# rcl_mini.net
KiCad netlist of a schematic drawn in EAGLE
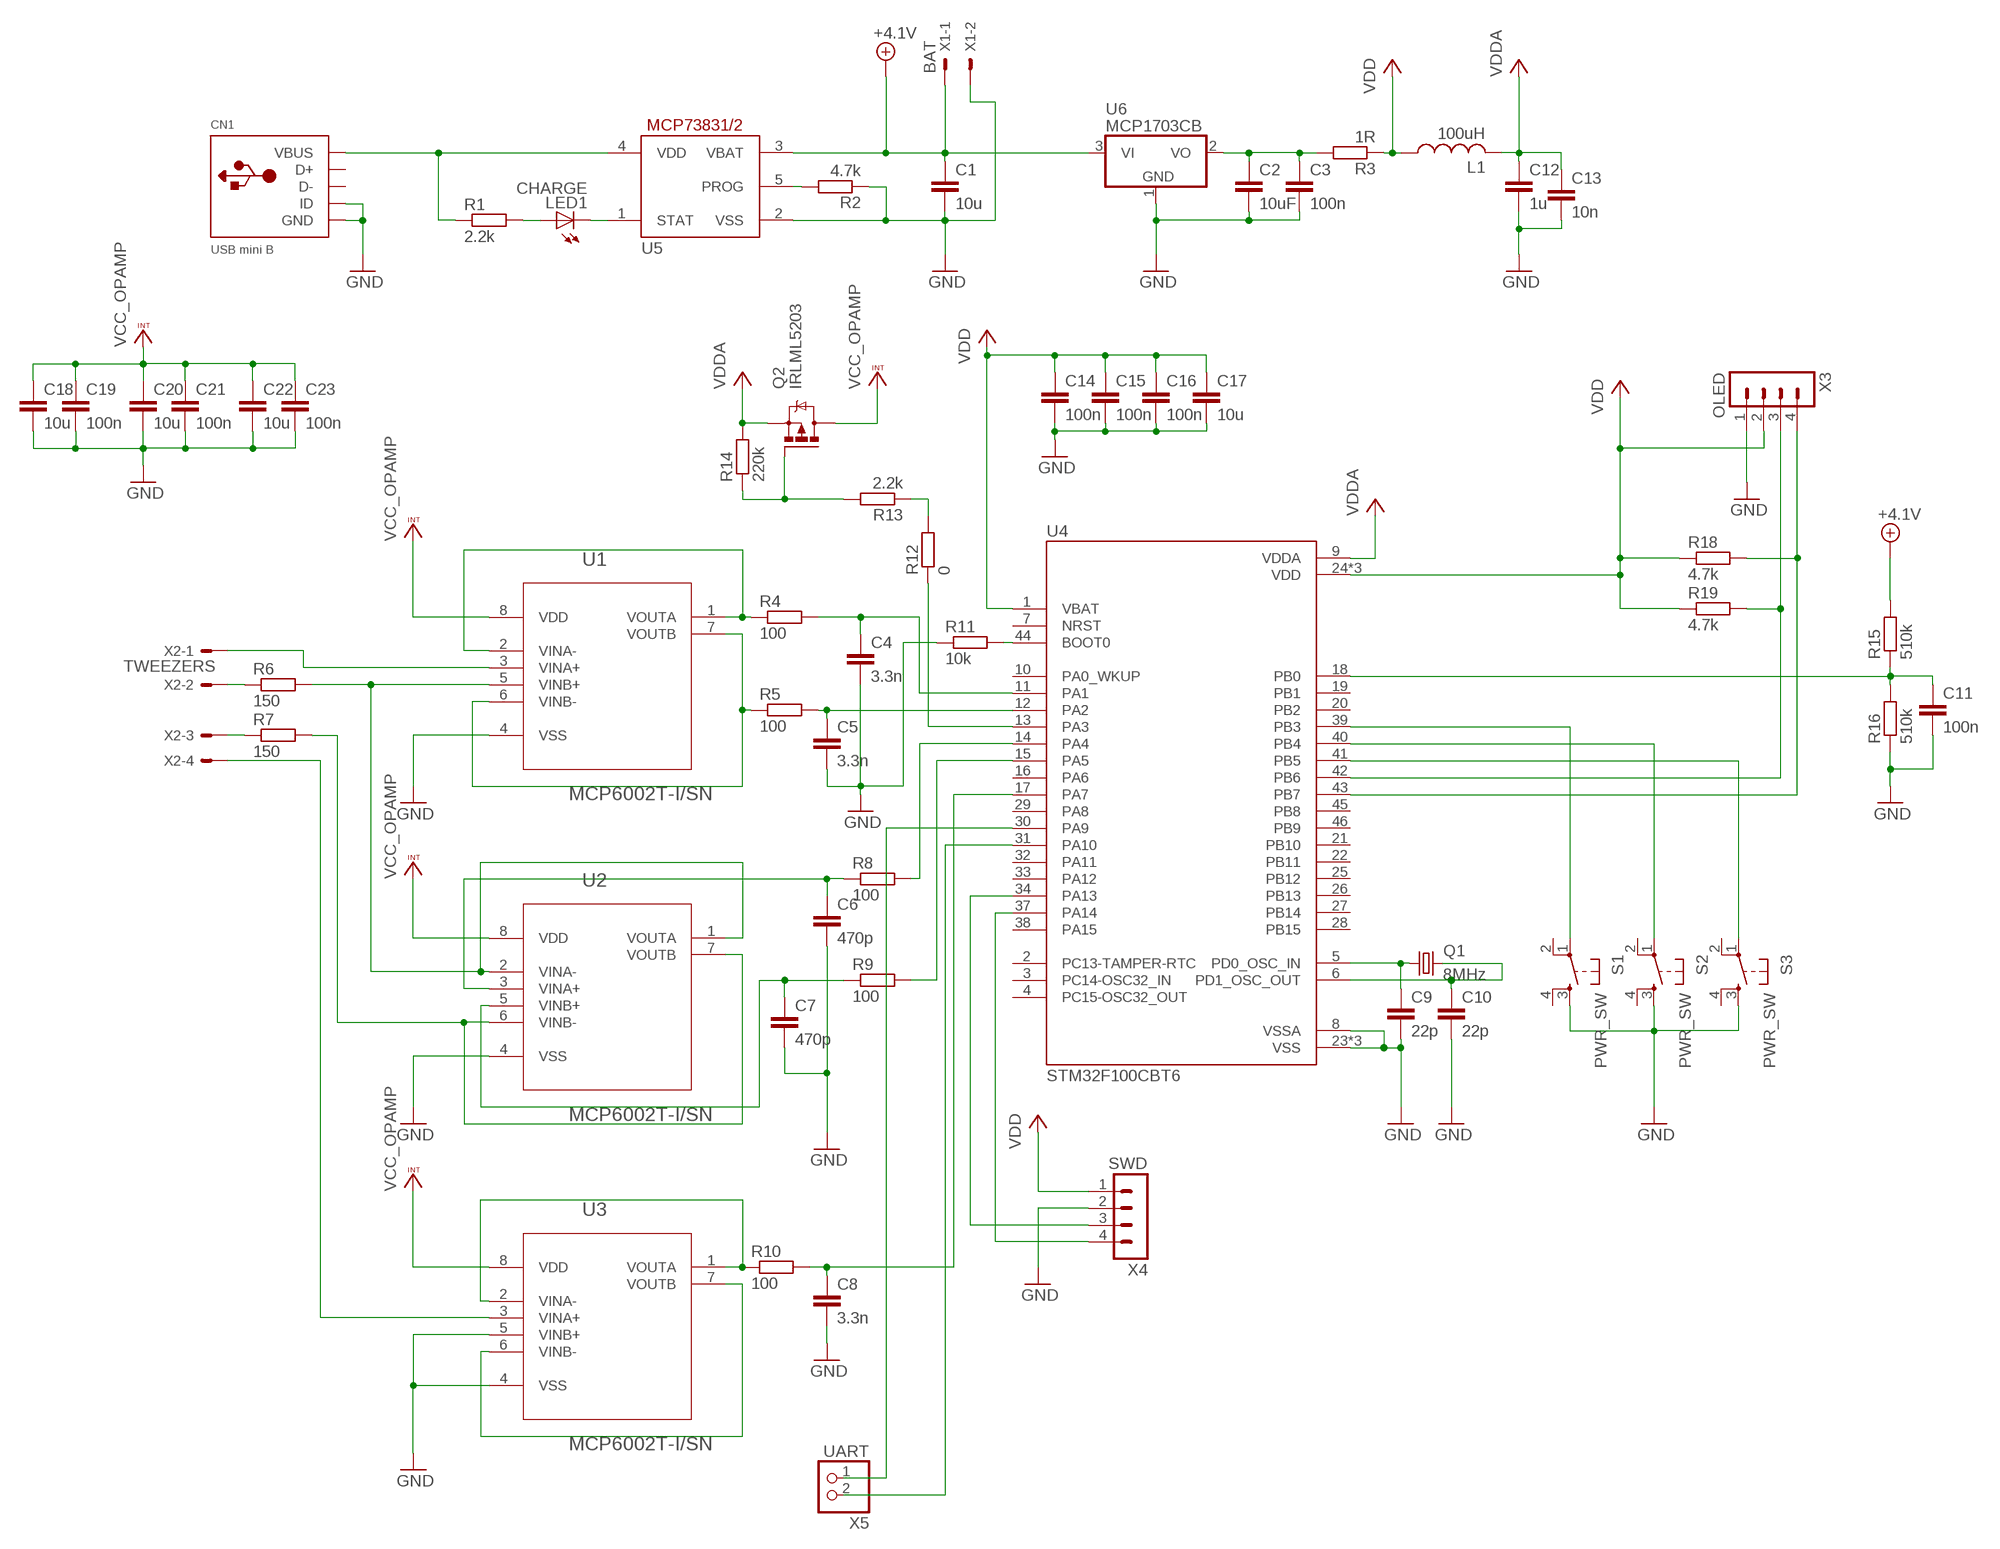
[diagram p0: schematic, sheet 1]

(export (version "E")
  (design (tool "Eeschema 10.0.6"))
  (components
    (comp (ref "C1")
      (value "10u")
      (footprint "eagle-import:C0805")
      (libsource (lib "eagle-import") (part "C-EUC0805"))
    )
    (comp (ref "C2")
      (value "10uF")
      (footprint "eagle-import:C0805")
      (libsource (lib "eagle-import") (part "C-EUC0805"))
    )
    (comp (ref "C3")
      (value "100n")
      (footprint "eagle-import:C0805")
      (libsource (lib "eagle-import") (part "C-EUC0805"))
    )
    (comp (ref "C4")
      (value "3.3n")
      (footprint "eagle-import:C0805")
      (libsource (lib "eagle-import") (part "C-EUC0805"))
    )
    (comp (ref "C5")
      (value "3.3n")
      (footprint "eagle-import:C0805")
      (libsource (lib "eagle-import") (part "C-EUC0805"))
    )
    (comp (ref "C6")
      (value "470p")
      (footprint "eagle-import:C0805")
      (libsource (lib "eagle-import") (part "C-EUC0805"))
    )
    (comp (ref "C7")
      (value "470p")
      (footprint "eagle-import:C0805")
      (libsource (lib "eagle-import") (part "C-EUC0805"))
    )
    (comp (ref "C8")
      (value "3.3n")
      (footprint "eagle-import:C0805")
      (libsource (lib "eagle-import") (part "C-EUC0805"))
    )
    (comp (ref "C9")
      (value "22p")
      (footprint "eagle-import:C0805")
      (libsource (lib "eagle-import") (part "C-EUC0805"))
    )
    (comp (ref "C10")
      (value "22p")
      (footprint "eagle-import:C0805")
      (libsource (lib "eagle-import") (part "C-EUC0805"))
    )
    (comp (ref "C11")
      (value "100n")
      (footprint "eagle-import:C0805")
      (libsource (lib "eagle-import") (part "C-EUC0805"))
    )
    (comp (ref "C12")
      (value "1u")
      (footprint "eagle-import:C0805")
      (libsource (lib "eagle-import") (part "C-EUC0805"))
    )
    (comp (ref "C13")
      (value "10n")
      (footprint "eagle-import:C0805")
      (libsource (lib "eagle-import") (part "C-EUC0805"))
    )
    (comp (ref "C14")
      (value "100n")
      (footprint "eagle-import:C0805")
      (libsource (lib "eagle-import") (part "C-EUC0805"))
    )
    (comp (ref "C15")
      (value "100n")
      (footprint "eagle-import:C0805")
      (libsource (lib "eagle-import") (part "C-EUC0805"))
    )
    (comp (ref "C16")
      (value "100n")
      (footprint "eagle-import:C0805")
      (libsource (lib "eagle-import") (part "C-EUC0805"))
    )
    (comp (ref "C17")
      (value "10u")
      (footprint "eagle-import:C0805")
      (libsource (lib "eagle-import") (part "C-EUC0805"))
    )
    (comp (ref "C18")
      (value "10u")
      (footprint "eagle-import:C0805")
      (libsource (lib "eagle-import") (part "C-EUC0805"))
    )
    (comp (ref "C19")
      (value "100n")
      (footprint "eagle-import:C0805")
      (libsource (lib "eagle-import") (part "C-EUC0805"))
    )
    (comp (ref "C20")
      (value "10u")
      (footprint "eagle-import:C0805")
      (libsource (lib "eagle-import") (part "C-EUC0805"))
    )
    (comp (ref "C21")
      (value "100n")
      (footprint "eagle-import:C0805")
      (libsource (lib "eagle-import") (part "C-EUC0805"))
    )
    (comp (ref "C22")
      (value "10u")
      (footprint "eagle-import:C0805")
      (libsource (lib "eagle-import") (part "C-EUC0805"))
    )
    (comp (ref "C23")
      (value "100n")
      (footprint "eagle-import:C0805")
      (libsource (lib "eagle-import") (part "C-EUC0805"))
    )
    (comp (ref "CN1")
      (value "USB mini B")
      (footprint "eagle-import:USB-MINIB")
      (libsource (lib "eagle-import") (part "USBMINIB"))
    )
    (comp (ref "L1")
      (value "100uH")
      (footprint "eagle-import:L3216C")
      (libsource (lib "eagle-import") (part "L-USL3216C"))
    )
    (comp (ref "LED1")
      (value "CHARGE")
      (footprint "eagle-import:CHIPLED_1206")
      (libsource (lib "eagle-import") (part "LEDCHIPLED_1206"))
    )
    (comp (ref "Q1")
      (value "8MHz")
      (footprint "eagle-import:HC49UP")
      (libsource (lib "eagle-import") (part "CRYSTALHC49UP"))
    )
    (comp (ref "Q2")
      (value "IRLML5203")
      (footprint "eagle-import:MICRO3")
      (libsource (lib "eagle-import") (part "IRLML5203"))
    )
    (comp (ref "R1")
      (value "2.2k")
      (footprint "eagle-import:M0805")
      (libsource (lib "eagle-import") (part "R-EU_M0805"))
    )
    (comp (ref "R2")
      (value "4.7k")
      (footprint "eagle-import:M0805")
      (libsource (lib "eagle-import") (part "R-EU_M0805"))
    )
    (comp (ref "R3")
      (value "1R")
      (footprint "eagle-import:M0805")
      (libsource (lib "eagle-import") (part "R-EU_M0805"))
    )
    (comp (ref "R4")
      (value "100")
      (footprint "eagle-import:M0805")
      (libsource (lib "eagle-import") (part "R-EU_M0805"))
    )
    (comp (ref "R5")
      (value "100")
      (footprint "eagle-import:M0805")
      (libsource (lib "eagle-import") (part "R-EU_M0805"))
    )
    (comp (ref "R6")
      (value "150")
      (footprint "eagle-import:M0805")
      (libsource (lib "eagle-import") (part "R-EU_M0805"))
    )
    (comp (ref "R7")
      (value "150")
      (footprint "eagle-import:M0805")
      (libsource (lib "eagle-import") (part "R-EU_M0805"))
    )
    (comp (ref "R8")
      (value "100")
      (footprint "eagle-import:M0805")
      (libsource (lib "eagle-import") (part "R-EU_M0805"))
    )
    (comp (ref "R9")
      (value "100")
      (footprint "eagle-import:M0805")
      (libsource (lib "eagle-import") (part "R-EU_M0805"))
    )
    (comp (ref "R10")
      (value "100")
      (footprint "eagle-import:M0805")
      (libsource (lib "eagle-import") (part "R-EU_M0805"))
    )
    (comp (ref "R11")
      (value "10k")
      (footprint "eagle-import:M0805")
      (libsource (lib "eagle-import") (part "R-EU_M0805"))
    )
    (comp (ref "R12")
      (value "0")
      (footprint "eagle-import:R1206")
      (libsource (lib "eagle-import") (part "R-EU_R1206"))
    )
    (comp (ref "R13")
      (value "2.2k")
      (footprint "eagle-import:M0805")
      (libsource (lib "eagle-import") (part "R-EU_M0805"))
    )
    (comp (ref "R14")
      (value "220k")
      (footprint "eagle-import:M0805")
      (libsource (lib "eagle-import") (part "R-EU_M0805"))
    )
    (comp (ref "R15")
      (value "510k")
      (footprint "eagle-import:M0805")
      (libsource (lib "eagle-import") (part "R-EU_M0805"))
    )
    (comp (ref "R16")
      (value "510k")
      (footprint "eagle-import:M0805")
      (libsource (lib "eagle-import") (part "R-EU_M0805"))
    )
    (comp (ref "R18")
      (value "4.7k")
      (footprint "eagle-import:M0805")
      (libsource (lib "eagle-import") (part "R-EU_M0805"))
    )
    (comp (ref "R19")
      (value "4.7k")
      (footprint "eagle-import:M0805")
      (libsource (lib "eagle-import") (part "R-EU_M0805"))
    )
    (comp (ref "S1")
      (value "PWR_SW")
      (footprint "eagle-import:DTS-6")
      (libsource (lib "eagle-import") (part "DTS-6"))
    )
    (comp (ref "S2")
      (value "PWR_SW")
      (footprint "eagle-import:DTS-6")
      (libsource (lib "eagle-import") (part "DTS-6"))
    )
    (comp (ref "S3")
      (value "PWR_SW")
      (footprint "eagle-import:DTS-6")
      (libsource (lib "eagle-import") (part "DTS-6"))
    )
    (comp (ref "U1")
      (value "MCP6002T-I/SN")
      (footprint "eagle-import:SOIC127P600X175-8N")
      (fields (field (name "MF") "Microchip") (field (name "MP") "MCP6002-E/SN"))
      (libsource (lib "eagle-import") (part "MCP6002-E/SN"))
    )
    (comp (ref "U2")
      (value "MCP6002T-I/SN")
      (footprint "eagle-import:SOIC127P600X175-8N")
      (fields (field (name "MF") "Microchip") (field (name "MP") "MCP6002-E/SN"))
      (libsource (lib "eagle-import") (part "MCP6002-E/SN"))
    )
    (comp (ref "U3")
      (value "MCP6002T-I/SN")
      (footprint "eagle-import:SOIC127P600X175-8N")
      (fields (field (name "MF") "Microchip") (field (name "MP") "MCP6002-E/SN"))
      (libsource (lib "eagle-import") (part "MCP6002-E/SN"))
    )
    (comp (ref "U4")
      (value "STM32F100CBT6")
      (footprint "eagle-import:QFP50P900X900X160-48N")
      (fields (field (name "MF") "STMicroelectronics") (field (name "MP") "STM32F103C8T6"))
      (libsource (lib "eagle-import") (part "STM32F103C8T6"))
    )
    (comp (ref "U5")
      (value "MCP73831/OT")
      (footprint "eagle-import:SOT23-5L")
      (libsource (lib "eagle-import") (part "MCP73831/OT"))
    )
    (comp (ref "U6")
      (value "MCP1703CB")
      (footprint "eagle-import:SOT23")
      (libsource (lib "eagle-import") (part "MCP1703CB"))
    )
    (comp (ref "UART")
      (value "X5")
      (footprint "eagle-import:1X02")
      (libsource (lib "eagle-import") (part "PINHD-1X2"))
    )
    (comp (ref "X1")
      (value "BAT")
      (footprint "eagle-import:22-23-2021")
      (fields (field (name "MF") "MOLEX") (field (name "MPN") "22-23-2021"))
      (libsource (lib "eagle-import") (part "22-23-2021"))
    )
    (comp (ref "X2")
      (value "TWEEZERS")
      (footprint "eagle-import:22-23-2041")
      (fields (field (name "MF") "MOLEX") (field (name "MPN") "22-23-2041"))
      (libsource (lib "eagle-import") (part "22-23-2041"))
    )
    (comp (ref "X3")
      (value "OLED")
      (footprint "eagle-import:MA04-1")
      (libsource (lib "eagle-import") (part "MA04-1"))
    )
    (comp (ref "X4")
      (value "SWD")
      (footprint "eagle-import:MA04-1")
      (libsource (lib "eagle-import") (part "MA04-1"))
    )
  )
  (nets
    (net (code "1") (name "+4.1V") (class "Default")
      (node (ref "C1") (pin "1") (pinfunction "1_1") (pintype "passive"))
      (node (ref "R15") (pin "2") (pinfunction "2_2") (pintype "passive"))
      (node (ref "U5") (pin "3") (pinfunction "VBAT_3") (pintype "bidirectional"))
      (node (ref "U6") (pin "3") (pinfunction "VI_3") (pintype "input"))
      (node (ref "X1") (pin "1") (pinfunction "S_1") (pintype "passive"))
    )
    (net (code "2") (name "GND") (class "Default")
      (node (ref "C1") (pin "2") (pinfunction "2_2") (pintype "passive"))
      (node (ref "C10") (pin "2") (pinfunction "2_2") (pintype "passive"))
      (node (ref "C11") (pin "2") (pinfunction "2_2") (pintype "passive"))
      (node (ref "C12") (pin "2") (pinfunction "2_2") (pintype "passive"))
      (node (ref "C13") (pin "2") (pinfunction "2_2") (pintype "passive"))
      (node (ref "C14") (pin "2") (pinfunction "2_2") (pintype "passive"))
      (node (ref "C15") (pin "2") (pinfunction "2_2") (pintype "passive"))
      (node (ref "C16") (pin "2") (pinfunction "2_2") (pintype "passive"))
      (node (ref "C17") (pin "2") (pinfunction "2_2") (pintype "passive"))
      (node (ref "C18") (pin "2") (pinfunction "2_2") (pintype "passive"))
      (node (ref "C19") (pin "2") (pinfunction "2_2") (pintype "passive"))
      (node (ref "C2") (pin "2") (pinfunction "2_2") (pintype "passive"))
      (node (ref "C20") (pin "2") (pinfunction "2_2") (pintype "passive"))
      (node (ref "C21") (pin "2") (pinfunction "2_2") (pintype "passive"))
      (node (ref "C22") (pin "2") (pinfunction "2_2") (pintype "passive"))
      (node (ref "C23") (pin "2") (pinfunction "2_2") (pintype "passive"))
      (node (ref "C3") (pin "2") (pinfunction "2_2") (pintype "passive"))
      (node (ref "C4") (pin "2") (pinfunction "2_2") (pintype "passive"))
      (node (ref "C5") (pin "2") (pinfunction "2_2") (pintype "passive"))
      (node (ref "C6") (pin "2") (pinfunction "2_2") (pintype "passive"))
      (node (ref "C7") (pin "2") (pinfunction "2_2") (pintype "passive"))
      (node (ref "C8") (pin "2") (pinfunction "2_2") (pintype "passive"))
      (node (ref "C9") (pin "2") (pinfunction "2_2") (pintype "passive"))
      (node (ref "CN1") (pin "GND") (pinfunction "GND_GND") (pintype "power_in"))
      (node (ref "CN1") (pin "ID") (pinfunction "ID_ID") (pintype "bidirectional"))
      (node (ref "R11") (pin "1") (pinfunction "1_1") (pintype "passive"))
      (node (ref "R16") (pin "1") (pinfunction "1_1") (pintype "passive"))
      (node (ref "R2") (pin "1") (pinfunction "1_1") (pintype "passive"))
      (node (ref "S1") (pin "3") (pinfunction "3_3") (pintype "passive"))
      (node (ref "S2") (pin "3") (pinfunction "3_3") (pintype "passive"))
      (node (ref "S3") (pin "3") (pinfunction "3_3") (pintype "passive"))
      (node (ref "U1") (pin "4") (pinfunction "VSS_4") (pintype "power_in"))
      (node (ref "U2") (pin "4") (pinfunction "VSS_4") (pintype "power_in"))
      (node (ref "U3") (pin "4") (pinfunction "VSS_4") (pintype "power_in"))
      (node (ref "U3") (pin "5") (pinfunction "VINB+_5") (pintype "input"))
      (node (ref "U4") (pin "23") (pinfunction "VSS_23") (pintype "power_in"))
      (node (ref "U4") (pin "35") (pinfunction "VSS_35") (pintype "power_in"))
      (node (ref "U4") (pin "47") (pinfunction "VSS_47") (pintype "power_in"))
      (node (ref "U4") (pin "8") (pinfunction "VSSA_8") (pintype "power_in"))
      (node (ref "U5") (pin "2") (pinfunction "VSS_2") (pintype "power_in"))
      (node (ref "U6") (pin "1") (pinfunction "GND_1") (pintype "passive"))
      (node (ref "X1") (pin "2") (pinfunction "S_2") (pintype "passive"))
      (node (ref "X3") (pin "1") (pinfunction "1_1") (pintype "passive"))
      (node (ref "X4") (pin "2") (pinfunction "2_2") (pintype "passive"))
    )
    (net (code "3") (name "Net-(LED1-PadA)") (class "Default")
      (node (ref "LED1") (pin "A") (pinfunction "A_A") (pintype "passive"))
      (node (ref "R1") (pin "2") (pinfunction "2_2") (pintype "passive"))
    )
    (net (code "4") (name "Net-(Q2-G)") (class "Default")
      (node (ref "Q2") (pin "1") (pinfunction "G_1") (pintype "passive"))
      (node (ref "R13") (pin "2") (pinfunction "2_2") (pintype "passive"))
      (node (ref "R14") (pin "1") (pinfunction "1_1") (pintype "passive"))
    )
    (net (code "5") (name "Net-(R12-Pad2)") (class "Default")
      (node (ref "R12") (pin "2") (pinfunction "2_2") (pintype "passive"))
      (node (ref "R13") (pin "1") (pinfunction "1_1") (pintype "passive"))
    )
    (net (code "6") (name "Net-(U1-VINA+)") (class "Default")
      (node (ref "U1") (pin "3") (pinfunction "VINA+_3") (pintype "input"))
      (node (ref "X2") (pin "1") (pinfunction "S_1") (pintype "passive"))
    )
    (net (code "7") (name "Net-(U1-VINA-)") (class "Default")
      (node (ref "R4") (pin "1") (pinfunction "1_1") (pintype "passive"))
      (node (ref "U1") (pin "1") (pinfunction "VOUTA_1") (pintype "output"))
      (node (ref "U1") (pin "2") (pinfunction "VINA-_2") (pintype "input"))
    )
    (net (code "8") (name "Net-(U1-VINB+)") (class "Default")
      (node (ref "R6") (pin "2") (pinfunction "2_2") (pintype "passive"))
      (node (ref "U1") (pin "5") (pinfunction "VINB+_5") (pintype "input"))
      (node (ref "U2") (pin "1") (pinfunction "VOUTA_1") (pintype "output"))
      (node (ref "U2") (pin "2") (pinfunction "VINA-_2") (pintype "input"))
    )
    (net (code "9") (name "Net-(U1-VINB-)") (class "Default")
      (node (ref "R5") (pin "1") (pinfunction "1_1") (pintype "passive"))
      (node (ref "U1") (pin "6") (pinfunction "VINB-_6") (pintype "input"))
      (node (ref "U1") (pin "7") (pinfunction "VOUTB_7") (pintype "output"))
    )
    (net (code "10") (name "Net-(U2-VINA+)") (class "Default")
      (node (ref "C6") (pin "1") (pinfunction "1_1") (pintype "passive"))
      (node (ref "R8") (pin "1") (pinfunction "1_1") (pintype "passive"))
      (node (ref "U2") (pin "3") (pinfunction "VINA+_3") (pintype "input"))
    )
    (net (code "11") (name "Net-(U2-VINB+)") (class "Default")
      (node (ref "C7") (pin "1") (pinfunction "1_1") (pintype "passive"))
      (node (ref "R9") (pin "1") (pinfunction "1_1") (pintype "passive"))
      (node (ref "U2") (pin "5") (pinfunction "VINB+_5") (pintype "input"))
    )
    (net (code "12") (name "Net-(U2-VINB-)") (class "Default")
      (node (ref "R7") (pin "2") (pinfunction "2_2") (pintype "passive"))
      (node (ref "U2") (pin "6") (pinfunction "VINB-_6") (pintype "input"))
      (node (ref "U2") (pin "7") (pinfunction "VOUTB_7") (pintype "output"))
    )
    (net (code "13") (name "Net-(U3-VINA+)") (class "Default")
      (node (ref "U3") (pin "3") (pinfunction "VINA+_3") (pintype "input"))
      (node (ref "X2") (pin "4") (pinfunction "S_4") (pintype "passive"))
    )
    (net (code "14") (name "Net-(U3-VINA-)") (class "Default")
      (node (ref "R10") (pin "1") (pinfunction "1_1") (pintype "passive"))
      (node (ref "U3") (pin "1") (pinfunction "VOUTA_1") (pintype "output"))
      (node (ref "U3") (pin "2") (pinfunction "VINA-_2") (pintype "input"))
    )
    (net (code "15") (name "Net-(U3-VINB-)") (class "Default")
      (node (ref "U3") (pin "6") (pinfunction "VINB-_6") (pintype "input"))
      (node (ref "U3") (pin "7") (pinfunction "VOUTB_7") (pintype "output"))
    )
    (net (code "16") (name "Net-(U4-BOOT0)") (class "Default")
      (node (ref "R11") (pin "2") (pinfunction "2_2") (pintype "passive"))
      (node (ref "U4") (pin "44") (pinfunction "BOOT0_44") (pintype "input"))
    )
    (net (code "17") (name "Net-(U4-PA1)") (class "Default")
      (node (ref "C4") (pin "1") (pinfunction "1_1") (pintype "passive"))
      (node (ref "R4") (pin "2") (pinfunction "2_2") (pintype "passive"))
      (node (ref "U4") (pin "11") (pinfunction "PA1_11") (pintype "bidirectional"))
    )
    (net (code "18") (name "Net-(U4-PA2)") (class "Default")
      (node (ref "C5") (pin "1") (pinfunction "1_1") (pintype "passive"))
      (node (ref "R5") (pin "2") (pinfunction "2_2") (pintype "passive"))
      (node (ref "U4") (pin "12") (pinfunction "PA2_12") (pintype "bidirectional"))
    )
    (net (code "19") (name "Net-(U4-PA3)") (class "Default")
      (node (ref "R12") (pin "1") (pinfunction "1_1") (pintype "passive"))
      (node (ref "U4") (pin "13") (pinfunction "PA3_13") (pintype "bidirectional"))
    )
    (net (code "20") (name "Net-(U4-PA4)") (class "Default")
      (node (ref "R8") (pin "2") (pinfunction "2_2") (pintype "passive"))
      (node (ref "U4") (pin "14") (pinfunction "PA4_14") (pintype "bidirectional"))
    )
    (net (code "21") (name "Net-(U4-PA5)") (class "Default")
      (node (ref "R9") (pin "2") (pinfunction "2_2") (pintype "passive"))
      (node (ref "U4") (pin "15") (pinfunction "PA5_15") (pintype "bidirectional"))
    )
    (net (code "22") (name "Net-(U4-PA7)") (class "Default")
      (node (ref "C8") (pin "1") (pinfunction "1_1") (pintype "passive"))
      (node (ref "R10") (pin "2") (pinfunction "2_2") (pintype "passive"))
      (node (ref "U4") (pin "17") (pinfunction "PA7_17") (pintype "bidirectional"))
    )
    (net (code "23") (name "Net-(U4-PA9)") (class "Default")
      (node (ref "U4") (pin "30") (pinfunction "PA9_30") (pintype "bidirectional"))
      (node (ref "UART") (pin "1") (pinfunction "1_1") (pintype "passive"))
    )
    (net (code "24") (name "Net-(U4-PA10)") (class "Default")
      (node (ref "U4") (pin "31") (pinfunction "PA10_31") (pintype "bidirectional"))
      (node (ref "UART") (pin "2") (pinfunction "2_2") (pintype "passive"))
    )
    (net (code "25") (name "Net-(U4-PA13)") (class "Default")
      (node (ref "U4") (pin "34") (pinfunction "PA13_34") (pintype "bidirectional"))
      (node (ref "X4") (pin "3") (pinfunction "3_3") (pintype "passive"))
    )
    (net (code "26") (name "Net-(U4-PA14)") (class "Default")
      (node (ref "U4") (pin "37") (pinfunction "PA14_37") (pintype "bidirectional"))
      (node (ref "X4") (pin "4") (pinfunction "4_4") (pintype "passive"))
    )
    (net (code "27") (name "Net-(U4-PB0)") (class "Default")
      (node (ref "C11") (pin "1") (pinfunction "1_1") (pintype "passive"))
      (node (ref "R15") (pin "1") (pinfunction "1_1") (pintype "passive"))
      (node (ref "R16") (pin "2") (pinfunction "2_2") (pintype "passive"))
      (node (ref "U4") (pin "18") (pinfunction "PB0_18") (pintype "bidirectional"))
    )
    (net (code "28") (name "Net-(U4-PB3)") (class "Default")
      (node (ref "S1") (pin "1") (pinfunction "1_1") (pintype "passive"))
      (node (ref "U4") (pin "39") (pinfunction "PB3_39") (pintype "bidirectional"))
    )
    (net (code "29") (name "Net-(U4-PB4)") (class "Default")
      (node (ref "S2") (pin "1") (pinfunction "1_1") (pintype "passive"))
      (node (ref "U4") (pin "40") (pinfunction "PB4_40") (pintype "bidirectional"))
    )
    (net (code "30") (name "Net-(U4-PB5)") (class "Default")
      (node (ref "S3") (pin "1") (pinfunction "1_1") (pintype "passive"))
      (node (ref "U4") (pin "41") (pinfunction "PB5_41") (pintype "bidirectional"))
    )
    (net (code "31") (name "Net-(U4-PB6)") (class "Default")
      (node (ref "R19") (pin "2") (pinfunction "2_2") (pintype "passive"))
      (node (ref "U4") (pin "42") (pinfunction "PB6_42") (pintype "bidirectional"))
      (node (ref "X3") (pin "3") (pinfunction "3_3") (pintype "passive"))
    )
    (net (code "32") (name "Net-(U4-PB7)") (class "Default")
      (node (ref "R18") (pin "2") (pinfunction "2_2") (pintype "passive"))
      (node (ref "U4") (pin "43") (pinfunction "PB7_43") (pintype "bidirectional"))
      (node (ref "X3") (pin "4") (pinfunction "4_4") (pintype "passive"))
    )
    (net (code "33") (name "Net-(U4-PD0_OSC_IN)") (class "Default")
      (node (ref "C9") (pin "1") (pinfunction "1_1") (pintype "passive"))
      (node (ref "Q1") (pin "1") (pinfunction "1_1") (pintype "passive"))
      (node (ref "U4") (pin "5") (pinfunction "PD0_OSC_IN_5") (pintype "bidirectional"))
    )
    (net (code "34") (name "Net-(U4-PD1_OSC_OUT)") (class "Default")
      (node (ref "C10") (pin "1") (pinfunction "1_1") (pintype "passive"))
      (node (ref "Q1") (pin "2") (pinfunction "2_2") (pintype "passive"))
      (node (ref "U4") (pin "6") (pinfunction "PD1_OSC_OUT_6") (pintype "bidirectional"))
    )
    (net (code "35") (name "Net-(U5-PROG)") (class "Default")
      (node (ref "R2") (pin "2") (pinfunction "2_2") (pintype "passive"))
      (node (ref "U5") (pin "5") (pinfunction "PROG_5") (pintype "input"))
    )
    (net (code "36") (name "Net-(U5-STAT)") (class "Default")
      (node (ref "LED1") (pin "C") (pinfunction "C_C") (pintype "passive"))
      (node (ref "U5") (pin "1") (pinfunction "STAT_1") (pintype "output"))
    )
    (net (code "37") (name "Net-(U5-VDD)") (class "Default")
      (node (ref "CN1") (pin "VBUS") (pinfunction "VBUS_VBUS") (pintype "power_in"))
      (node (ref "R1") (pin "1") (pinfunction "1_1") (pintype "passive"))
      (node (ref "U5") (pin "4") (pinfunction "VDD_4") (pintype "power_in"))
    )
    (net (code "38") (name "Net-(U6-VO)") (class "Default")
      (node (ref "C2") (pin "1") (pinfunction "1_1") (pintype "passive"))
      (node (ref "C3") (pin "1") (pinfunction "1_1") (pintype "passive"))
      (node (ref "R3") (pin "2") (pinfunction "2_2") (pintype "passive"))
      (node (ref "U6") (pin "2") (pinfunction "VO_2") (pintype "passive"))
    )
    (net (code "39") (name "Net-(X2B-S)") (class "Default")
      (node (ref "R6") (pin "1") (pinfunction "1_1") (pintype "passive"))
      (node (ref "X2") (pin "2") (pinfunction "S_2") (pintype "passive"))
    )
    (net (code "40") (name "Net-(X2C-S)") (class "Default")
      (node (ref "R7") (pin "1") (pinfunction "1_1") (pintype "passive"))
      (node (ref "X2") (pin "3") (pinfunction "S_3") (pintype "passive"))
    )
    (net (code "41") (name "VCC_OPAMP") (class "Default")
      (node (ref "C18") (pin "1") (pinfunction "1_1") (pintype "passive"))
      (node (ref "C19") (pin "1") (pinfunction "1_1") (pintype "passive"))
      (node (ref "C20") (pin "1") (pinfunction "1_1") (pintype "passive"))
      (node (ref "C21") (pin "1") (pinfunction "1_1") (pintype "passive"))
      (node (ref "C22") (pin "1") (pinfunction "1_1") (pintype "passive"))
      (node (ref "C23") (pin "1") (pinfunction "1_1") (pintype "passive"))
      (node (ref "Q2") (pin "3") (pinfunction "D_3") (pintype "passive"))
      (node (ref "U1") (pin "8") (pinfunction "VDD_8") (pintype "power_in"))
      (node (ref "U2") (pin "8") (pinfunction "VDD_8") (pintype "power_in"))
      (node (ref "U3") (pin "8") (pinfunction "VDD_8") (pintype "power_in"))
    )
    (net (code "42") (name "VDD") (class "Default")
      (node (ref "C14") (pin "1") (pinfunction "1_1") (pintype "passive"))
      (node (ref "C15") (pin "1") (pinfunction "1_1") (pintype "passive"))
      (node (ref "C16") (pin "1") (pinfunction "1_1") (pintype "passive"))
      (node (ref "C17") (pin "1") (pinfunction "1_1") (pintype "passive"))
      (node (ref "L1") (pin "1") (pinfunction "1_1") (pintype "passive"))
      (node (ref "R18") (pin "1") (pinfunction "1_1") (pintype "passive"))
      (node (ref "R19") (pin "1") (pinfunction "1_1") (pintype "passive"))
      (node (ref "R3") (pin "1") (pinfunction "1_1") (pintype "passive"))
      (node (ref "U4") (pin "1") (pinfunction "VBAT_1") (pintype "bidirectional"))
      (node (ref "U4") (pin "24") (pinfunction "VDD_24") (pintype "power_in"))
      (node (ref "U4") (pin "36") (pinfunction "VDD_36") (pintype "power_in"))
      (node (ref "U4") (pin "48") (pinfunction "VDD_48") (pintype "power_in"))
      (node (ref "X3") (pin "2") (pinfunction "2_2") (pintype "passive"))
      (node (ref "X4") (pin "1") (pinfunction "1_1") (pintype "passive"))
    )
    (net (code "43") (name "VDDA") (class "Default")
      (node (ref "C12") (pin "1") (pinfunction "1_1") (pintype "passive"))
      (node (ref "C13") (pin "1") (pinfunction "1_1") (pintype "passive"))
      (node (ref "L1") (pin "2") (pinfunction "2_2") (pintype "passive"))
      (node (ref "Q2") (pin "2") (pinfunction "S_2") (pintype "passive"))
      (node (ref "R14") (pin "2") (pinfunction "2_2") (pintype "passive"))
      (node (ref "U4") (pin "9") (pinfunction "VDDA_9") (pintype "power_in"))
    )
    (net (code "44") (name "unconnected-(CN1-PadD+)") (class "Default")
      (node (ref "CN1") (pin "D+") (pinfunction "D+_D+") (pintype "bidirectional"))
    )
    (net (code "45") (name "unconnected-(CN1-PadD-)") (class "Default")
      (node (ref "CN1") (pin "D-") (pinfunction "D-_D-") (pintype "bidirectional"))
    )
    (net (code "46") (name "unconnected-(S1-Pad2)") (class "Default")
      (node (ref "S1") (pin "2") (pinfunction "2_2") (pintype "passive"))
    )
    (net (code "47") (name "unconnected-(S1-Pad4)") (class "Default")
      (node (ref "S1") (pin "4") (pinfunction "4_4") (pintype "passive"))
    )
    (net (code "48") (name "unconnected-(S2-Pad2)") (class "Default")
      (node (ref "S2") (pin "2") (pinfunction "2_2") (pintype "passive"))
    )
    (net (code "49") (name "unconnected-(S2-Pad4)") (class "Default")
      (node (ref "S2") (pin "4") (pinfunction "4_4") (pintype "passive"))
    )
    (net (code "50") (name "unconnected-(S3-Pad2)") (class "Default")
      (node (ref "S3") (pin "2") (pinfunction "2_2") (pintype "passive"))
    )
    (net (code "51") (name "unconnected-(S3-Pad4)") (class "Default")
      (node (ref "S3") (pin "4") (pinfunction "4_4") (pintype "passive"))
    )
    (net (code "52") (name "unconnected-(U4-NRST-Pad7)") (class "Default")
      (node (ref "U4") (pin "7") (pinfunction "NRST_7") (pintype "input"))
    )
    (net (code "53") (name "unconnected-(U4-PA0_WKUP-Pad10)") (class "Default")
      (node (ref "U4") (pin "10") (pinfunction "PA0_WKUP_10") (pintype "bidirectional"))
    )
    (net (code "54") (name "unconnected-(U4-PA6-Pad16)") (class "Default")
      (node (ref "U4") (pin "16") (pinfunction "PA6_16") (pintype "bidirectional"))
    )
    (net (code "55") (name "unconnected-(U4-PA8-Pad29)") (class "Default")
      (node (ref "U4") (pin "29") (pinfunction "PA8_29") (pintype "bidirectional"))
    )
    (net (code "56") (name "unconnected-(U4-PA11-Pad32)") (class "Default")
      (node (ref "U4") (pin "32") (pinfunction "PA11_32") (pintype "bidirectional"))
    )
    (net (code "57") (name "unconnected-(U4-PA12-Pad33)") (class "Default")
      (node (ref "U4") (pin "33") (pinfunction "PA12_33") (pintype "bidirectional"))
    )
    (net (code "58") (name "unconnected-(U4-PA15-Pad38)") (class "Default")
      (node (ref "U4") (pin "38") (pinfunction "PA15_38") (pintype "bidirectional"))
    )
    (net (code "59") (name "unconnected-(U4-PB1-Pad19)") (class "Default")
      (node (ref "U4") (pin "19") (pinfunction "PB1_19") (pintype "bidirectional"))
    )
    (net (code "60") (name "unconnected-(U4-PB2-Pad20)") (class "Default")
      (node (ref "U4") (pin "20") (pinfunction "PB2_20") (pintype "bidirectional"))
    )
    (net (code "61") (name "unconnected-(U4-PB8-Pad45)") (class "Default")
      (node (ref "U4") (pin "45") (pinfunction "PB8_45") (pintype "bidirectional"))
    )
    (net (code "62") (name "unconnected-(U4-PB9-Pad46)") (class "Default")
      (node (ref "U4") (pin "46") (pinfunction "PB9_46") (pintype "bidirectional"))
    )
    (net (code "63") (name "unconnected-(U4-PB10-Pad21)") (class "Default")
      (node (ref "U4") (pin "21") (pinfunction "PB10_21") (pintype "bidirectional"))
    )
    (net (code "64") (name "unconnected-(U4-PB11-Pad22)") (class "Default")
      (node (ref "U4") (pin "22") (pinfunction "PB11_22") (pintype "bidirectional"))
    )
    (net (code "65") (name "unconnected-(U4-PB12-Pad25)") (class "Default")
      (node (ref "U4") (pin "25") (pinfunction "PB12_25") (pintype "bidirectional"))
    )
    (net (code "66") (name "unconnected-(U4-PB13-Pad26)") (class "Default")
      (node (ref "U4") (pin "26") (pinfunction "PB13_26") (pintype "bidirectional"))
    )
    (net (code "67") (name "unconnected-(U4-PB14-Pad27)") (class "Default")
      (node (ref "U4") (pin "27") (pinfunction "PB14_27") (pintype "bidirectional"))
    )
    (net (code "68") (name "unconnected-(U4-PB15-Pad28)") (class "Default")
      (node (ref "U4") (pin "28") (pinfunction "PB15_28") (pintype "bidirectional"))
    )
    (net (code "69") (name "unconnected-(U4-PC13-TAMPER-RTC-Pad2)") (class "Default")
      (node (ref "U4") (pin "2") (pinfunction "PC13-TAMPER-RTC_2") (pintype "bidirectional"))
    )
    (net (code "70") (name "unconnected-(U4-PC14-OSC32_IN-Pad3)") (class "Default")
      (node (ref "U4") (pin "3") (pinfunction "PC14-OSC32_IN_3") (pintype "bidirectional"))
    )
    (net (code "71") (name "unconnected-(U4-PC15-OSC32_OUT-Pad4)") (class "Default")
      (node (ref "U4") (pin "4") (pinfunction "PC15-OSC32_OUT_4") (pintype "bidirectional"))
    )
  )
)
